# CAN_Breakout.net
KiCad netlist of a schematic drawn in Altium Designer
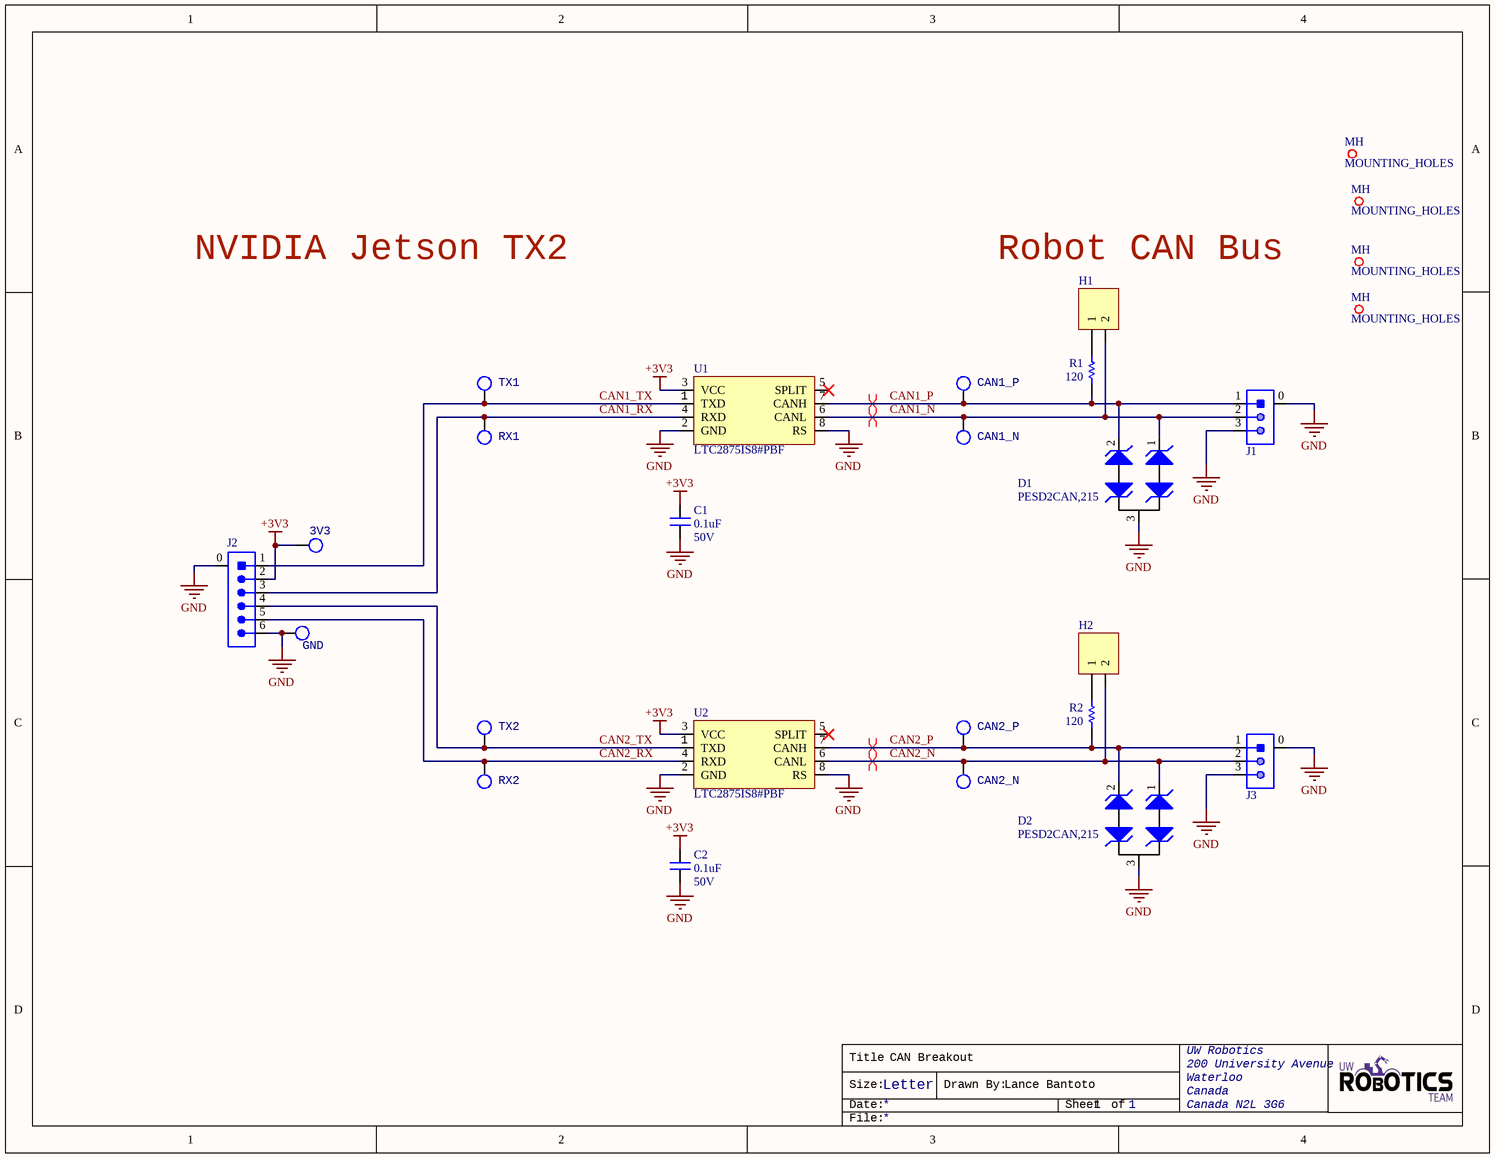
[diagram p0: CAN Breakout.SchDoc]

(export (version "E")
  (design (tool "Eeschema 10.0.6"))
  (components
    (comp (ref "3V3")
      (value "TESTPOINT_LOOP")
      (footprint "TESTPOINT_LOOP")
      (description "Loop testpoint through-hole pad")
      (libsource (lib "UWRT_Schematic_Library_2020") (part "TESTPOINT_LOOP"))
    )
    (comp (ref "C1")
      (value "0.1uF")
      (footprint "CAPC2012X140N")
      (description "CAP CER 0.1UF 50V X7R 0805")
      (fields
        (field (name "VOLTAGE RATING") "50V")
        (field (name "TOLERANCE") "10%")
        (field (name "Comment") "CAP_0.1uF_50V_0805")
      )
      (libsource (lib "UWRT_Schematic_Library_2020") (part "CAP_0.1uF_50V_0805"))
    )
    (comp (ref "C2")
      (value "0.1uF")
      (footprint "CAPC2012X140N")
      (description "CAP CER 0.1UF 50V X7R 0805")
      (fields
        (field (name "VOLTAGE RATING") "50V")
        (field (name "TOLERANCE") "10%")
        (field (name "Comment") "CAP_0.1uF_50V_0805")
      )
      (libsource (lib "UWRT_Schematic_Library_2020") (part "CAP_0.1uF_50V_0805"))
    )
    (comp (ref "CAN1_N")
      (value "TESTPOINT_LOOP")
      (footprint "TESTPOINT_LOOP")
      (description "Loop testpoint through-hole pad")
      (libsource (lib "UWRT_Schematic_Library_2020") (part "TESTPOINT_LOOP"))
    )
    (comp (ref "CAN1_P")
      (value "TESTPOINT_LOOP")
      (footprint "TESTPOINT_LOOP")
      (description "Loop testpoint through-hole pad")
      (libsource (lib "UWRT_Schematic_Library_2020") (part "TESTPOINT_LOOP"))
    )
    (comp (ref "CAN2_N")
      (value "TESTPOINT_LOOP")
      (footprint "TESTPOINT_LOOP")
      (description "Loop testpoint through-hole pad")
      (libsource (lib "UWRT_Schematic_Library_2020") (part "TESTPOINT_LOOP"))
    )
    (comp (ref "CAN2_P")
      (value "TESTPOINT_LOOP")
      (footprint "TESTPOINT_LOOP")
      (description "Loop testpoint through-hole pad")
      (libsource (lib "UWRT_Schematic_Library_2020") (part "TESTPOINT_LOOP"))
    )
    (comp (ref "D1")
      (value "TVS_DIODE_CAN")
      (footprint "TVS_DIODE_CAN")
      (description "TVS DIODE 24V 41V SOT323-3")
      (fields (field (name "MANUFACTURER PART NUMBER 1") "PESD2CAN,215"))
      (libsource (lib "UWRT_Schematic_Library_2020") (part "TVS_DIODE_CAN"))
    )
    (comp (ref "D2")
      (value "TVS_DIODE_CAN")
      (footprint "TVS_DIODE_CAN")
      (description "TVS DIODE 24V 41V SOT323-3")
      (fields (field (name "MANUFACTURER PART NUMBER 1") "PESD2CAN,215"))
      (libsource (lib "UWRT_Schematic_Library_2020") (part "TVS_DIODE_CAN"))
    )
    (comp (ref "GND")
      (value "TESTPOINT_LOOP")
      (footprint "TESTPOINT_LOOP")
      (description "Loop testpoint through-hole pad")
      (libsource (lib "UWRT_Schematic_Library_2020") (part "TESTPOINT_LOOP"))
    )
    (comp (ref "H1")
      (value "JUMPER_2")
      (footprint "HDR1X2")
      (description "HEADER 2X1")
      (libsource (lib "UWRT_Schematic_Library_2020") (part "JUMPER_2"))
    )
    (comp (ref "H2")
      (value "JUMPER_2")
      (footprint "HDR1X2")
      (description "HEADER 2X1")
      (libsource (lib "UWRT_Schematic_Library_2020") (part "JUMPER_2"))
    )
    (comp (ref "J1")
      (value "CON_3M_SM4")
      (footprint "JST-B3B-SM4-TB")
      (description "CONN HEADER SMD 3POS 2MM")
      (libsource (lib "UWRT_Schematic_Library_2020") (part "CON_3M_SM4"))
    )
    (comp (ref "J2")
      (value "CON_6M_SM4")
      (footprint "JST-B6B-SM4-TB")
      (description "CONN HEADER SMD 6POS 2MM")
      (fields
        (field (name "MANUFACTURER PART NUMBER") "B6B-PH-SM4-TB(LF)(SN)")
        (field (name "MANUFACTURER") "JST")
      )
      (libsource (lib "UWRT_Schematic_Library_2020") (part "CON_6M_SM4"))
    )
    (comp (ref "J3")
      (value "CON_3M_SM4")
      (footprint "JST-B3B-SM4-TB")
      (description "CONN HEADER SMD 3POS 2MM")
      (libsource (lib "UWRT_Schematic_Library_2020") (part "CON_3M_SM4"))
    )
    (comp (ref "R1")
      (value "120")
      (footprint "RESC2012X60N")
      (description "RES SMD 120 OHM 1% 1/8W 0805")
      (fields (field (name "RESISTANCE") "120"))
      (libsource (lib "UWRT_Schematic_Library_2020") (part "RES_120R_0805"))
    )
    (comp (ref "R2")
      (value "120")
      (footprint "RESC2012X60N")
      (description "RES SMD 120 OHM 1% 1/8W 0805")
      (fields (field (name "RESISTANCE") "120"))
      (libsource (lib "UWRT_Schematic_Library_2020") (part "RES_120R_0805"))
    )
    (comp (ref "RX1")
      (value "TESTPOINT_LOOP")
      (footprint "TESTPOINT_LOOP")
      (description "Loop testpoint through-hole pad")
      (libsource (lib "UWRT_Schematic_Library_2020") (part "TESTPOINT_LOOP"))
    )
    (comp (ref "RX2")
      (value "TESTPOINT_LOOP")
      (footprint "TESTPOINT_LOOP")
      (description "Loop testpoint through-hole pad")
      (libsource (lib "UWRT_Schematic_Library_2020") (part "TESTPOINT_LOOP"))
    )
    (comp (ref "TX1")
      (value "TESTPOINT_LOOP")
      (footprint "TESTPOINT_LOOP")
      (description "Loop testpoint through-hole pad")
      (libsource (lib "UWRT_Schematic_Library_2020") (part "TESTPOINT_LOOP"))
    )
    (comp (ref "TX2")
      (value "TESTPOINT_LOOP")
      (footprint "TESTPOINT_LOOP")
      (description "Loop testpoint through-hole pad")
      (libsource (lib "UWRT_Schematic_Library_2020") (part "TESTPOINT_LOOP"))
    )
    (comp (ref "U1")
      (value "IC TXRX CAN")
      (footprint "LT-S8_N")
      (description "IC TXRX CAN 4MBPS 8SO")
      (fields (field (name "MANUFACTURER PART NUMBER 1") "LTC2875IS8#PBF"))
      (libsource (lib "UWRT_Schematic_Library_2020") (part "LTC2875"))
    )
    (comp (ref "U2")
      (value "IC TXRX CAN")
      (footprint "LT-S8_N")
      (description "IC TXRX CAN 4MBPS 8SO")
      (fields (field (name "MANUFACTURER PART NUMBER 1") "LTC2875IS8#PBF"))
      (libsource (lib "UWRT_Schematic_Library_2020") (part "LTC2875"))
    )
  )
  (nets
    (net (code "1") (name "+3V3") (class "Default")
      (node (ref "3V3") (pin "1") (pintype "passive"))
      (node (ref "C1") (pin "2") (pinfunction "2_2") (pintype "passive"))
      (node (ref "C2") (pin "2") (pinfunction "2_2") (pintype "passive"))
      (node (ref "J2") (pin "2") (pinfunction "2_2") (pintype "passive"))
      (node (ref "U1") (pin "3") (pinfunction "VCC_3") (pintype "passive"))
      (node (ref "U2") (pin "3") (pinfunction "VCC_3") (pintype "passive"))
    )
    (net (code "2") (name "/CAN1_N") (class "Default")
      (node (ref "CAN1_N") (pin "1") (pintype "passive"))
      (node (ref "D1") (pin "1") (pinfunction "1_1") (pintype "passive"))
      (node (ref "H1") (pin "2") (pinfunction "2_2") (pintype "passive"))
      (node (ref "J1") (pin "2") (pinfunction "2_2") (pintype "passive"))
      (node (ref "U1") (pin "6") (pinfunction "CANL_6") (pintype "passive"))
    )
    (net (code "3") (name "/CAN1_P") (class "Default")
      (node (ref "CAN1_P") (pin "1") (pintype "passive"))
      (node (ref "D1") (pin "2") (pinfunction "2_2") (pintype "passive"))
      (node (ref "J1") (pin "1") (pinfunction "1_1") (pintype "passive"))
      (node (ref "R1") (pin "1") (pinfunction "1_1") (pintype "passive"))
      (node (ref "U1") (pin "7") (pinfunction "CANH_7") (pintype "passive"))
    )
    (net (code "4") (name "/CAN1_RX") (class "Default")
      (node (ref "J2") (pin "3") (pinfunction "3_3") (pintype "passive"))
      (node (ref "RX1") (pin "1") (pintype "passive"))
      (node (ref "U1") (pin "4") (pinfunction "RXD_4") (pintype "passive"))
    )
    (net (code "5") (name "/CAN1_TX") (class "Default")
      (node (ref "J2") (pin "1") (pinfunction "1_1") (pintype "passive"))
      (node (ref "TX1") (pin "1") (pintype "passive"))
      (node (ref "U1") (pin "1") (pinfunction "TXD_1") (pintype "passive"))
    )
    (net (code "6") (name "/CAN2_N") (class "Default")
      (node (ref "CAN2_N") (pin "1") (pintype "passive"))
      (node (ref "D2") (pin "1") (pinfunction "1_1") (pintype "passive"))
      (node (ref "H2") (pin "2") (pinfunction "2_2") (pintype "passive"))
      (node (ref "J3") (pin "2") (pinfunction "2_2") (pintype "passive"))
      (node (ref "U2") (pin "6") (pinfunction "CANL_6") (pintype "passive"))
    )
    (net (code "7") (name "/CAN2_P") (class "Default")
      (node (ref "CAN2_P") (pin "1") (pintype "passive"))
      (node (ref "D2") (pin "2") (pinfunction "2_2") (pintype "passive"))
      (node (ref "J3") (pin "1") (pinfunction "1_1") (pintype "passive"))
      (node (ref "R2") (pin "1") (pinfunction "1_1") (pintype "passive"))
      (node (ref "U2") (pin "7") (pinfunction "CANH_7") (pintype "passive"))
    )
    (net (code "8") (name "/CAN2_RX") (class "Default")
      (node (ref "J2") (pin "5") (pinfunction "5_5") (pintype "passive"))
      (node (ref "RX2") (pin "1") (pintype "passive"))
      (node (ref "U2") (pin "4") (pinfunction "RXD_4") (pintype "passive"))
    )
    (net (code "9") (name "/CAN2_TX") (class "Default")
      (node (ref "J2") (pin "4") (pinfunction "4_4") (pintype "passive"))
      (node (ref "TX2") (pin "1") (pintype "passive"))
      (node (ref "U2") (pin "1") (pinfunction "TXD_1") (pintype "passive"))
    )
    (net (code "10") (name "GND") (class "Default")
      (node (ref "C1") (pin "1") (pinfunction "1_1") (pintype "passive"))
      (node (ref "C2") (pin "1") (pinfunction "1_1") (pintype "passive"))
      (node (ref "D1") (pin "3") (pinfunction "3_3") (pintype "passive"))
      (node (ref "D2") (pin "3") (pinfunction "3_3") (pintype "passive"))
      (node (ref "GND") (pin "1") (pintype "passive"))
      (node (ref "J1") (pin "0") (pinfunction "0_0") (pintype "passive"))
      (node (ref "J1") (pin "3") (pinfunction "3_3") (pintype "passive"))
      (node (ref "J2") (pin "0") (pinfunction "0_0") (pintype "passive"))
      (node (ref "J2") (pin "6") (pinfunction "6_6") (pintype "passive"))
      (node (ref "J3") (pin "0") (pinfunction "0_0") (pintype "passive"))
      (node (ref "J3") (pin "3") (pinfunction "3_3") (pintype "passive"))
      (node (ref "U1") (pin "2") (pinfunction "GND_2") (pintype "passive"))
      (node (ref "U1") (pin "8") (pinfunction "RS_8") (pintype "passive"))
      (node (ref "U2") (pin "2") (pinfunction "GND_2") (pintype "passive"))
      (node (ref "U2") (pin "8") (pinfunction "RS_8") (pintype "passive"))
    )
    (net (code "11") (name "Net-(H1-Pad1)") (class "Default")
      (node (ref "H1") (pin "1") (pinfunction "1_1") (pintype "passive"))
      (node (ref "R1") (pin "2") (pinfunction "2_2") (pintype "passive"))
    )
    (net (code "12") (name "Net-(H2-Pad1)") (class "Default")
      (node (ref "H2") (pin "1") (pinfunction "1_1") (pintype "passive"))
      (node (ref "R2") (pin "2") (pinfunction "2_2") (pintype "passive"))
    )
    (net (code "13") (name "unconnected-(U1-SPLIT-Pad5)") (class "Default")
      (node (ref "U1") (pin "5") (pinfunction "SPLIT_5") (pintype "passive+no_connect"))
    )
    (net (code "14") (name "unconnected-(U2-SPLIT-Pad5)") (class "Default")
      (node (ref "U2") (pin "5") (pinfunction "SPLIT_5") (pintype "passive+no_connect"))
    )
  )
)
